# IN_OUT_Switch.net
KiCad netlist of a schematic drawn in Altium Designer
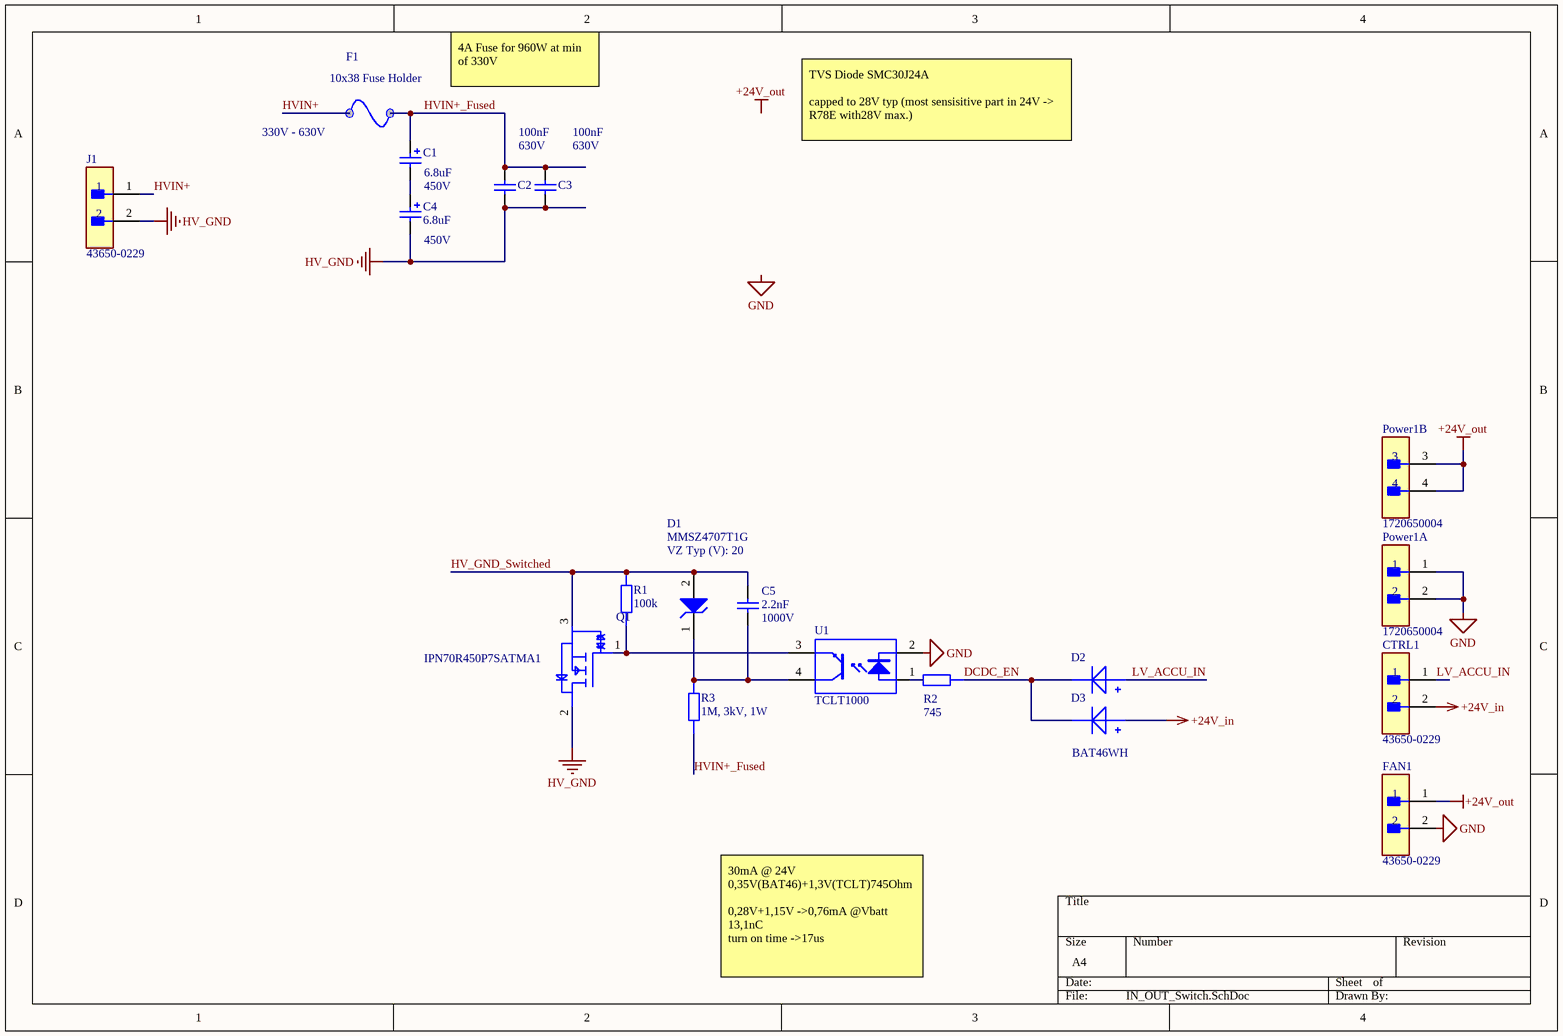
[diagram p0: IN_OUT_Switch.SchDoc]

(export (version "E")
  (design (tool "Eeschema 10.0.6"))
  (components
    (comp (ref "C1")
      (value "6.8uF")
      (footprint "WCAP-AT1H_D13H20")
      (description "WCAP-AT1H Aluminum Electrolytic Capacitor, Radial, THT, D13xH20mm, 6.8uF, 450V")
      (fields
        (field (name "MANUFACTURER PART NUMBER") "860241478002")
        (field (name "MANUFACTURER") "Wurth Elektronik")
        (field (name "VOLTAGE") "450V")
      )
      (libsource (lib "Altium_WCAP-AT1H (rev20b)") (part "860241478002"))
    )
    (comp (ref "C2")
      (value "~")
      (footprint "WCAP-CSMH_1812_H2")
      (description "WCAP-CSMH Multilayer Ceramic Chip Capacitor, size 1812, X7R Class II, 100nF, 630V")
      (fields
        (field (name "MANUFACTURER PART NUMBER") "885342211006")
        (field (name "CAPACITANCE") "100nF")
        (field (name "MANUFACTURER") "Wurth Elektronik")
        (field (name "VOLTAGE") "630V")
      )
      (libsource (lib "Altium_WCAP-CSMH (rev20a)") (part "885342211006"))
    )
    (comp (ref "C3")
      (value "~")
      (footprint "WCAP-CSMH_1812_H2")
      (description "WCAP-CSMH Multilayer Ceramic Chip Capacitor, size 1812, X7R Class II, 100nF, 630V")
      (fields
        (field (name "MANUFACTURER PART NUMBER") "885342211006")
        (field (name "CAPACITANCE") "100nF")
        (field (name "MANUFACTURER") "Wurth Elektronik")
        (field (name "VOLTAGE") "630V")
      )
      (libsource (lib "Altium_WCAP-CSMH (rev20a)") (part "885342211006"))
    )
    (comp (ref "C4")
      (value "6.8uF")
      (footprint "WCAP-AT1H_D13H20")
      (description "WCAP-AT1H Aluminum Electrolytic Capacitor, Radial, THT, D13xH20mm, 6.8uF, 450V")
      (fields
        (field (name "MANUFACTURER PART NUMBER") "860241478002")
        (field (name "MANUFACTURER") "Wurth Elektronik")
        (field (name "VOLTAGE") "450V")
      )
      (libsource (lib "Altium_WCAP-AT1H (rev20b)") (part "860241478002"))
    )
    (comp (ref "C5")
      (value "~")
      (footprint "WCAP-CSMH_0805_H1.25")
      (description "WCAP-CSMH Multilayer Ceramic Chip Capacitor, size 0805, X7R Class II, 2.2nF, 1000V")
      (fields
        (field (name "MANUFACTURER PART NUMBER") "885342207016")
        (field (name "CAPACITANCE") "2.2nF")
        (field (name "MANUFACTURER") "Wurth Elektronik")
        (field (name "VOLTAGE") "1000V")
      )
      (libsource (lib "Altium_WCAP-CSMH (rev20a)") (part "885342207016"))
    )
    (comp (ref "CTRL1")
      (value "43650-0229")
      (footprint "FP-43650-0229-MFG")
      (description "CONN HEADER VERT 2POS 3MM")
      (fields
        (field (name "OCTOPART") "https://octopart.com/43650-0229-molex-7652326")
        (field (name "MANUFACTURER") "Molex")
      )
      (libsource (lib "Altium Content Vault") (part "3bc925449376181038e59eaffc5286c"))
    )
    (comp (ref "D1")
      (value "MMSZ4707T1G")
      (footprint "ONSC-SOD-123-2-425-04_V")
      (description "Zener Voltage Regulator, 500 mW, 2-Pin SOD-123, Pb-Free, Tape and Reel")
      (fields (field (name "MANUFACTURER") "On Semiconductor") (field (name "VZ TYP (V)") "20"))
      (libsource (lib "Altium Content Vault") (part "ONSC-K1A2-2"))
    )
    (comp (ref "D2")
      (value "BAT46WH")
      (footprint "DIOM2715X18N")
      (libsource (lib "Integrated_LibraryLukas_New") (part "BAT46WH"))
    )
    (comp (ref "D3")
      (value "BAT46WH")
      (footprint "DIOM2715X18N")
      (libsource (lib "Integrated_LibraryLukas_New") (part "BAT46WH"))
    )
    (comp (ref "F1")
      (value "10x38 Fuse Holder")
      (footprint "10x38 Fuse")
      (libsource (lib "Integrated_LibraryLukas_New") (part "10x38 Fuse Holder"))
    )
    (comp (ref "FAN1")
      (value "43650-0229")
      (footprint "FP-43650-0229-MFG")
      (description "CONN HEADER VERT 2POS 3MM")
      (fields
        (field (name "OCTOPART") "https://octopart.com/43650-0229-molex-7652326")
        (field (name "MANUFACTURER") "Molex")
      )
      (libsource (lib "Altium Content Vault") (part "3bc925449376181038e59eaffc5286c"))
    )
    (comp (ref "J1")
      (value "43650-0229")
      (footprint "FP-43650-0229-MFG")
      (description "CONN HEADER VERT 2POS 3MM")
      (fields
        (field (name "OCTOPART") "https://octopart.com/43650-0229-molex-7652326")
        (field (name "MANUFACTURER") "Molex")
      )
      (libsource (lib "Altium Content Vault") (part "3bc925449376181038e59eaffc5286c"))
    )
    (comp (ref "Power1")
      (value "1720650004")
      (footprint "FP-1720650004-MFG")
      (description "CONN HEADER VERT 4POS 5.7MM")
      (fields
        (field (name "MANUFACTURER") "Molex")
        (field (name "OCTOPART") "https://octopart.com/172065-0004-molex-34473112")
      )
      (libsource (lib "Altium Content Vault") (part "ac72c5313ea981db199dbd0e8237b04"))
    )
    (comp (ref "Q1")
      (value "IPN70R450P7SATMA1")
      (footprint "SOT230P700X180-4L")
      (description "IPN70R450P7S Series 700 V 10 A 7.1 W CoolMOS P7 Power Transistor - PG-SOT-223")
      (fields (field (name "MANUFACTURER") "Infineon"))
      (libsource (lib "Integrated_LibraryLukas_New") (part "IPN70R450P7SATMA1"))
    )
    (comp (ref "R1")
      (value "100k")
      (footprint "STACKPOLE CSR0603")
      (description "Resistor with multiple footprints")
      (fields (field (name "Comment") "SMD Resistor"))
      (libsource (lib "Standardbauteile") (part "SMD Resistor"))
    )
    (comp (ref "R2")
      (value "745")
      (footprint "STACKPOLE CSR0603")
      (description "Resistor with multiple footprints")
      (fields (field (name "Comment") "SMD Resistor"))
      (libsource (lib "Standardbauteile") (part "SMD Resistor"))
    )
    (comp (ref "R3")
      (value "1M, 3kV, 1W")
      (footprint "STACKPOLE CSRN2512")
      (description "Resistor with multiple footprints")
      (fields (field (name "Comment") "CHV2512-FX-1004ELF"))
      (libsource (lib "Standardbauteile") (part "SMD Resistor"))
    )
    (comp (ref "U1")
      (value "TCLT1000")
      (footprint "VISH-SOP4L-4_V")
      (fields (field (name "MANUFACTURER") "Vishay/Semiconductor"))
      (libsource (lib "Altium Content Vault") (part "OPTO-ACEC-4"))
    )
  )
  (nets
    (net (code "1") (name "+24V_in") (class "Default")
      (node (ref "CTRL1") (pin "2") (pinfunction "2_2") (pintype "passive"))
      (node (ref "D3") (pin "1") (pintype "passive"))
    )
    (net (code "2") (name "+24V_out") (class "Default")
      (node (ref "FAN1") (pin "1") (pinfunction "1_1") (pintype "passive"))
      (node (ref "Power1") (pin "3") (pinfunction "3_3") (pintype "passive"))
      (node (ref "Power1") (pin "4") (pinfunction "4_4") (pintype "passive"))
    )
    (net (code "3") (name "/DCDC_EN") (class "Default")
      (node (ref "D2") (pin "2") (pintype "passive"))
      (node (ref "D3") (pin "2") (pintype "passive"))
      (node (ref "R2") (pin "2") (pinfunction "2_2") (pintype "passive"))
    )
    (net (code "4") (name "/HVIN+") (class "Default")
      (node (ref "F1") (pin "2") (pintype "passive"))
      (node (ref "J1") (pin "1") (pinfunction "1_1") (pintype "passive"))
    )
    (net (code "5") (name "/HVIN+_Fused") (class "Default")
      (node (ref "C1") (pin "1") (pinfunction "P_1") (pintype "passive"))
      (node (ref "C2") (pin "1") (pinfunction "1_1") (pintype "passive"))
      (node (ref "C3") (pin "1") (pinfunction "1_1") (pintype "passive"))
      (node (ref "F1") (pin "1") (pintype "passive"))
      (node (ref "R3") (pin "2") (pinfunction "2_2") (pintype "passive"))
    )
    (net (code "6") (name "/HV_GND_Switched") (class "Default")
      (node (ref "C5") (pin "2") (pinfunction "2_2") (pintype "passive"))
      (node (ref "D1") (pin "2") (pinfunction "A_2") (pintype "passive"))
      (node (ref "Q1") (pin "3") (pintype "passive"))
      (node (ref "R1") (pin "1") (pinfunction "1_1") (pintype "passive"))
    )
    (net (code "7") (name "/LV_ACCU_IN") (class "Default")
      (node (ref "CTRL1") (pin "1") (pinfunction "1_1") (pintype "passive"))
      (node (ref "D2") (pin "1") (pintype "passive"))
    )
    (net (code "8") (name "GND") (class "Default")
      (node (ref "FAN1") (pin "2") (pinfunction "2_2") (pintype "passive"))
      (node (ref "Power1") (pin "1") (pinfunction "1_1") (pintype "passive"))
      (node (ref "Power1") (pin "2") (pinfunction "2_2") (pintype "passive"))
      (node (ref "U1") (pin "2") (pinfunction "C_2") (pintype "passive"))
    )
    (net (code "9") (name "HV_GND") (class "Default")
      (node (ref "C2") (pin "2") (pinfunction "2_2") (pintype "passive"))
      (node (ref "C3") (pin "2") (pinfunction "2_2") (pintype "passive"))
      (node (ref "C4") (pin "2") (pinfunction "N_2") (pintype "passive"))
      (node (ref "J1") (pin "2") (pinfunction "2_2") (pintype "passive"))
      (node (ref "Q1") (pin "2") (pintype "passive"))
    )
    (net (code "10") (name "Net-(C1-N)") (class "Default")
      (node (ref "C1") (pin "2") (pinfunction "N_2") (pintype "passive"))
      (node (ref "C4") (pin "1") (pinfunction "P_1") (pintype "passive"))
    )
    (net (code "11") (name "Net-(D1-K)") (class "Default")
      (node (ref "C5") (pin "1") (pinfunction "1_1") (pintype "passive"))
      (node (ref "D1") (pin "1") (pinfunction "K_1") (pintype "passive"))
      (node (ref "R3") (pin "1") (pinfunction "1_1") (pintype "passive"))
      (node (ref "U1") (pin "4") (pinfunction "C_4") (pintype "passive"))
    )
    (net (code "12") (name "Net-(U1-A)") (class "Default")
      (node (ref "R2") (pin "1") (pinfunction "1_1") (pintype "passive"))
      (node (ref "U1") (pin "1") (pinfunction "A_1") (pintype "passive"))
    )
    (net (code "13") (name "Net-(U1-E)") (class "Default")
      (node (ref "Q1") (pin "1") (pintype "passive"))
      (node (ref "R1") (pin "2") (pinfunction "2_2") (pintype "passive"))
      (node (ref "U1") (pin "3") (pinfunction "E_3") (pintype "passive"))
    )
  )
)
